# V21-Selector-Keyboard-Relay-K-R-RevD-S.net
KiCad netlist of a schematic drawn in EAGLE
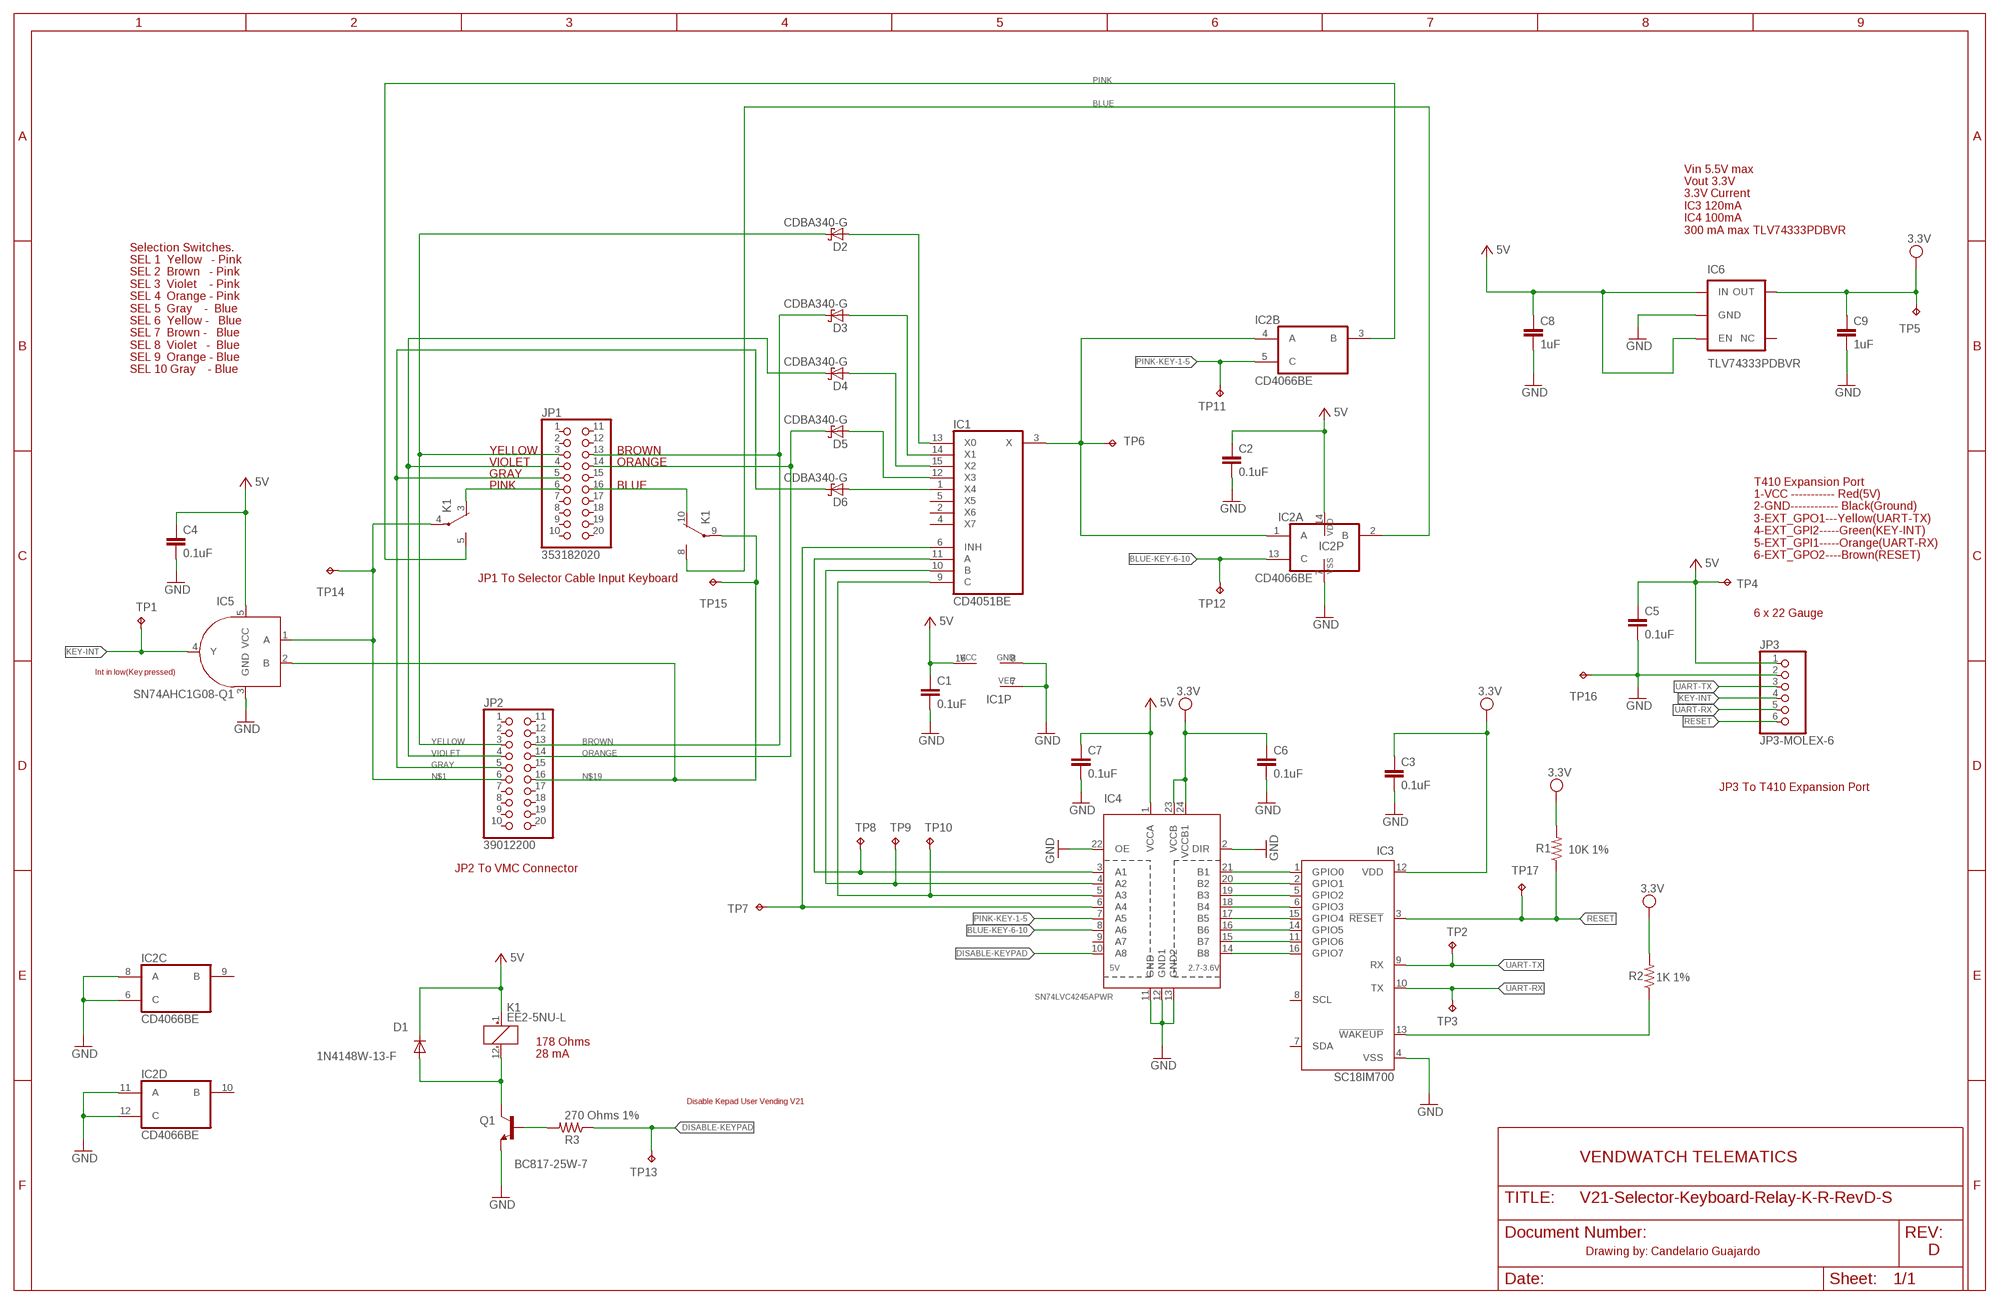
[diagram p0: schematic, sheet 1]

(export (version "E")
  (design (tool "Eeschema 10.0.6"))
  (components
    (comp (ref "C1")
      (value "0.1uF")
      (footprint "eagle-import:0805")
      (libsource (lib "eagle-import") (part "CAP0805"))
    )
    (comp (ref "C2")
      (value "0.1uF")
      (footprint "eagle-import:0805")
      (libsource (lib "eagle-import") (part "CAP0805"))
    )
    (comp (ref "C3")
      (value "0.1uF")
      (footprint "eagle-import:0805")
      (libsource (lib "eagle-import") (part "CAP0805"))
    )
    (comp (ref "C4")
      (value "0.1uF")
      (footprint "eagle-import:0805")
      (libsource (lib "eagle-import") (part "CAP0805"))
    )
    (comp (ref "C5")
      (value "0.1uF")
      (footprint "eagle-import:0805")
      (libsource (lib "eagle-import") (part "CAP0805"))
    )
    (comp (ref "C6")
      (value "0.1uF")
      (footprint "eagle-import:0805")
      (libsource (lib "eagle-import") (part "CAP0805"))
    )
    (comp (ref "C7")
      (value "0.1uF")
      (footprint "eagle-import:0805")
      (libsource (lib "eagle-import") (part "CAP0805"))
    )
    (comp (ref "C8")
      (value "1uF")
      (footprint "eagle-import:0805")
      (libsource (lib "eagle-import") (part "CAP0805"))
    )
    (comp (ref "C9")
      (value "1uF")
      (footprint "eagle-import:0805")
      (libsource (lib "eagle-import") (part "CAP0805"))
    )
    (comp (ref "D1")
      (value "1N4148W-13-F")
      (footprint "eagle-import:SOD-123")
      (libsource (lib "eagle-import") (part "DIODESOD-123"))
    )
    (comp (ref "D2")
      (value "CDBA340-G")
      (footprint "eagle-import:DO-214AC-SMA")
      (libsource (lib "eagle-import") (part "CDBA340-G"))
    )
    (comp (ref "D3")
      (value "CDBA340-G")
      (footprint "eagle-import:DO-214AC-SMA")
      (libsource (lib "eagle-import") (part "CDBA340-G"))
    )
    (comp (ref "D4")
      (value "CDBA340-G")
      (footprint "eagle-import:DO-214AC-SMA")
      (libsource (lib "eagle-import") (part "CDBA340-G"))
    )
    (comp (ref "D5")
      (value "CDBA340-G")
      (footprint "eagle-import:DO-214AC-SMA")
      (libsource (lib "eagle-import") (part "CDBA340-G"))
    )
    (comp (ref "D6")
      (value "CDBA340-G")
      (footprint "eagle-import:DO-214AC-SMA")
      (libsource (lib "eagle-import") (part "CDBA340-G"))
    )
    (comp (ref "IC1")
      (value "CD4051BE")
      (footprint "eagle-import:SO16")
      (libsource (lib "eagle-import") (part "4051D"))
    )
    (comp (ref "IC2")
      (value "CD4066BE")
      (footprint "eagle-import:SO14")
      (libsource (lib "eagle-import") (part "4066D"))
    )
    (comp (ref "IC3")
      (value "SC18IM700")
      (footprint "eagle-import:TSSOP16")
      (fields (field (name "MANUFACTURER") "NXP Semiconductors") (field (name "MPN") "SC18IM700IPW/S8HP"))
      (libsource (lib "eagle-import") (part "SC18IM700"))
    )
    (comp (ref "IC4")
      (value "SN74LVC4245APWR")
      (footprint "eagle-import:SOIC24")
      (libsource (lib "eagle-import") (part "SN74LVC4245"))
    )
    (comp (ref "IC5")
      (value "SN74AHC1G08-Q1")
      (footprint "eagle-import:SOT23-5")
      (libsource (lib "eagle-import") (part "74AHC1G08"))
    )
    (comp (ref "IC6")
      (value "TLV74333PDBVR")
      (footprint "eagle-import:SOT-23-5")
      (libsource (lib "eagle-import") (part "TLV74333PDBVR"))
    )
    (comp (ref "JP1")
      (value "353182020")
      (footprint "eagle-import:2X10-4.2MM-TH-RA")
      (libsource (lib "eagle-import") (part "353182020"))
    )
    (comp (ref "JP2")
      (value "39012200")
      (footprint "eagle-import:2X10-4.2MM-FS-CRIMP")
      (libsource (lib "eagle-import") (part "39012200"))
    )
    (comp (ref "JP3")
      (value "JP3-MOLEX-6")
      (footprint "eagle-import:HEADER-1X6-22-GAUGE-OVAL")
      (libsource (lib "eagle-import") (part "JP3-MOLEX-6"))
    )
    (comp (ref "K1")
      (value "EE2-5NU-L")
      (footprint "eagle-import:DPDT-2-FROM-C-EE2")
      (libsource (lib "eagle-import") (part "EE2-5NU-L"))
    )
    (comp (ref "Q1")
      (value "BC817-25W-7")
      (footprint "eagle-import:SOT323")
      (libsource (lib "eagle-import") (part "TRANSISTOR-NPN"))
    )
    (comp (ref "R1")
      (value "10K 1%")
      (footprint "eagle-import:0805")
      (libsource (lib "eagle-import") (part "RESISTOR0805-RES"))
    )
    (comp (ref "R2")
      (value "1K 1%")
      (footprint "eagle-import:0805")
      (libsource (lib "eagle-import") (part "RESISTOR0805-RES"))
    )
    (comp (ref "R3")
      (value "270 Ohms 1%")
      (footprint "eagle-import:0805")
      (libsource (lib "eagle-import") (part "RESISTOR0805-RES"))
    )
    (comp (ref "TP1")
      (value "TPB1,27")
      (footprint "eagle-import:B1,27")
      (libsource (lib "eagle-import") (part "TPB1,27"))
    )
    (comp (ref "TP2")
      (value "TPB1,27")
      (footprint "eagle-import:B1,27")
      (libsource (lib "eagle-import") (part "TPB1,27"))
    )
    (comp (ref "TP3")
      (value "TPB1,27")
      (footprint "eagle-import:B1,27")
      (libsource (lib "eagle-import") (part "TPB1,27"))
    )
    (comp (ref "TP4")
      (value "TPB1,27")
      (footprint "eagle-import:B1,27")
      (libsource (lib "eagle-import") (part "TPB1,27"))
    )
    (comp (ref "TP5")
      (value "TPB1,27")
      (footprint "eagle-import:B1,27")
      (libsource (lib "eagle-import") (part "TPB1,27"))
    )
    (comp (ref "TP6")
      (value "TPB1,27")
      (footprint "eagle-import:B1,27")
      (libsource (lib "eagle-import") (part "TPB1,27"))
    )
    (comp (ref "TP7")
      (value "TPB1,27")
      (footprint "eagle-import:B1,27")
      (libsource (lib "eagle-import") (part "TPB1,27"))
    )
    (comp (ref "TP8")
      (value "TPB1,27")
      (footprint "eagle-import:B1,27")
      (libsource (lib "eagle-import") (part "TPB1,27"))
    )
    (comp (ref "TP9")
      (value "TPB1,27")
      (footprint "eagle-import:B1,27")
      (libsource (lib "eagle-import") (part "TPB1,27"))
    )
    (comp (ref "TP10")
      (value "TPB1,27")
      (footprint "eagle-import:B1,27")
      (libsource (lib "eagle-import") (part "TPB1,27"))
    )
    (comp (ref "TP11")
      (value "TPB1,27")
      (footprint "eagle-import:B1,27")
      (libsource (lib "eagle-import") (part "TPB1,27"))
    )
    (comp (ref "TP12")
      (value "TPB1,27")
      (footprint "eagle-import:B1,27")
      (libsource (lib "eagle-import") (part "TPB1,27"))
    )
    (comp (ref "TP13")
      (value "TPB1,27")
      (footprint "eagle-import:B1,27")
      (libsource (lib "eagle-import") (part "TPB1,27"))
    )
    (comp (ref "TP14")
      (value "TPB1,27")
      (footprint "eagle-import:B1,27")
      (libsource (lib "eagle-import") (part "TPB1,27"))
    )
    (comp (ref "TP15")
      (value "TPB1,27")
      (footprint "eagle-import:B1,27")
      (libsource (lib "eagle-import") (part "TPB1,27"))
    )
    (comp (ref "TP16")
      (value "TPB1,27")
      (footprint "eagle-import:B1,27")
      (libsource (lib "eagle-import") (part "TPB1,27"))
    )
    (comp (ref "TP17")
      (value "TPB1,27")
      (footprint "eagle-import:B1,27")
      (libsource (lib "eagle-import") (part "TPB1,27"))
    )
  )
  (nets
    (net (code "1") (name "/BLUE") (class "Default")
      (node (ref "IC2") (pin "2") (pinfunction "B_2") (pintype "tri_state"))
      (node (ref "K1") (pin "8") (pinfunction "S_8") (pintype "passive"))
    )
    (net (code "2") (name "/BROWN") (class "Default")
      (node (ref "D3") (pin "K") (pinfunction "C_K") (pintype "passive"))
      (node (ref "JP1") (pin "13") (pinfunction "13_13") (pintype "passive"))
      (node (ref "JP2") (pin "13") (pinfunction "13_13") (pintype "passive"))
    )
    (net (code "3") (name "/GRAY") (class "Default")
      (node (ref "D6") (pin "K") (pinfunction "C_K") (pintype "passive"))
      (node (ref "JP1") (pin "5") (pinfunction "5_5") (pintype "passive"))
      (node (ref "JP2") (pin "5") (pinfunction "5_5") (pintype "passive"))
    )
    (net (code "4") (name "/N$1") (class "Default")
      (node (ref "IC5") (pin "1") (pinfunction "A_1") (pintype "bidirectional"))
      (node (ref "JP2") (pin "6") (pinfunction "6_6") (pintype "passive"))
      (node (ref "K1") (pin "4") (pinfunction "P_4") (pintype "passive"))
      (node (ref "TP14") (pin "TP") (pinfunction "TP_TP") (pintype "input"))
    )
    (net (code "5") (name "/N$19") (class "Default")
      (node (ref "IC5") (pin "2") (pinfunction "B_2") (pintype "bidirectional"))
      (node (ref "JP2") (pin "16") (pinfunction "16_16") (pintype "passive"))
      (node (ref "K1") (pin "9") (pinfunction "P_9") (pintype "passive"))
      (node (ref "TP15") (pin "TP") (pinfunction "TP_TP") (pintype "input"))
    )
    (net (code "6") (name "/ORANGE") (class "Default")
      (node (ref "D5") (pin "K") (pinfunction "C_K") (pintype "passive"))
      (node (ref "JP1") (pin "14") (pinfunction "14_14") (pintype "passive"))
      (node (ref "JP2") (pin "14") (pinfunction "14_14") (pintype "passive"))
    )
    (net (code "7") (name "/PINK") (class "Default")
      (node (ref "IC2") (pin "3") (pinfunction "B_3") (pintype "tri_state"))
      (node (ref "K1") (pin "5") (pinfunction "S_5") (pintype "passive"))
    )
    (net (code "8") (name "/VIOLET") (class "Default")
      (node (ref "D4") (pin "K") (pinfunction "C_K") (pintype "passive"))
      (node (ref "JP1") (pin "4") (pinfunction "4_4") (pintype "passive"))
      (node (ref "JP2") (pin "4") (pinfunction "4_4") (pintype "passive"))
    )
    (net (code "9") (name "/YELLOW") (class "Default")
      (node (ref "D2") (pin "K") (pinfunction "C_K") (pintype "passive"))
      (node (ref "JP1") (pin "3") (pinfunction "3_3") (pintype "passive"))
      (node (ref "JP2") (pin "3") (pinfunction "3_3") (pintype "passive"))
    )
    (net (code "10") (name "3.3V") (class "Default")
      (node (ref "C3") (pin "1") (pinfunction "1_1") (pintype "passive"))
      (node (ref "C6") (pin "1") (pinfunction "1_1") (pintype "passive"))
      (node (ref "C9") (pin "1") (pinfunction "1_1") (pintype "passive"))
      (node (ref "IC3") (pin "12") (pinfunction "VDD_12") (pintype "power_in"))
      (node (ref "IC4") (pin "23") (pinfunction "VCCB_23") (pintype "bidirectional"))
      (node (ref "IC4") (pin "24") (pinfunction "VCCB1_24") (pintype "bidirectional"))
      (node (ref "IC6") (pin "5") (pinfunction "OUT_5") (pintype "output"))
      (node (ref "R1") (pin "2") (pinfunction "2_2") (pintype "passive"))
      (node (ref "R2") (pin "2") (pinfunction "2_2") (pintype "passive"))
      (node (ref "TP5") (pin "TP") (pinfunction "TP_TP") (pintype "input"))
    )
    (net (code "11") (name "5V") (class "Default")
      (node (ref "C1") (pin "1") (pinfunction "1_1") (pintype "passive"))
      (node (ref "C2") (pin "1") (pinfunction "1_1") (pintype "passive"))
      (node (ref "C4") (pin "1") (pinfunction "1_1") (pintype "passive"))
      (node (ref "C5") (pin "1") (pinfunction "1_1") (pintype "passive"))
      (node (ref "C7") (pin "1") (pinfunction "1_1") (pintype "passive"))
      (node (ref "C8") (pin "1") (pinfunction "1_1") (pintype "passive"))
      (node (ref "D1") (pin "C") (pinfunction "C_C") (pintype "passive"))
      (node (ref "IC1") (pin "16") (pinfunction "VCC_16") (pintype "power_in"))
      (node (ref "IC2") (pin "14") (pinfunction "VDD_14") (pintype "power_in"))
      (node (ref "IC4") (pin "1") (pinfunction "VCCA_1") (pintype "bidirectional"))
      (node (ref "IC5") (pin "5") (pinfunction "VCC_5") (pintype "bidirectional"))
      (node (ref "IC6") (pin "1") (pinfunction "IN_1") (pintype "input"))
      (node (ref "IC6") (pin "3") (pinfunction "EN_3") (pintype "input"))
      (node (ref "JP3") (pin "1") (pinfunction "1_1") (pintype "passive"))
      (node (ref "K1") (pin "1") (pinfunction "+_1") (pintype "passive"))
      (node (ref "TP4") (pin "TP") (pinfunction "TP_TP") (pintype "input"))
    )
    (net (code "12") (name "BLUE-KEY-6-10") (class "Default")
      (node (ref "IC2") (pin "13") (pinfunction "C_13") (pintype "input"))
      (node (ref "IC4") (pin "8") (pinfunction "A6_8") (pintype "bidirectional"))
      (node (ref "TP12") (pin "TP") (pinfunction "TP_TP") (pintype "input"))
    )
    (net (code "13") (name "DISABLE-KEYPAD") (class "Default")
      (node (ref "IC4") (pin "10") (pinfunction "A8_10") (pintype "bidirectional"))
      (node (ref "R3") (pin "1") (pinfunction "1_1") (pintype "passive"))
      (node (ref "TP13") (pin "TP") (pinfunction "TP_TP") (pintype "input"))
    )
    (net (code "14") (name "GND") (class "Default")
      (node (ref "C1") (pin "2") (pinfunction "2_2") (pintype "passive"))
      (node (ref "C2") (pin "2") (pinfunction "2_2") (pintype "passive"))
      (node (ref "C3") (pin "2") (pinfunction "2_2") (pintype "passive"))
      (node (ref "C4") (pin "2") (pinfunction "2_2") (pintype "passive"))
      (node (ref "C5") (pin "2") (pinfunction "2_2") (pintype "passive"))
      (node (ref "C6") (pin "2") (pinfunction "2_2") (pintype "passive"))
      (node (ref "C7") (pin "2") (pinfunction "2_2") (pintype "passive"))
      (node (ref "C8") (pin "2") (pinfunction "2_2") (pintype "passive"))
      (node (ref "C9") (pin "2") (pinfunction "2_2") (pintype "passive"))
      (node (ref "IC1") (pin "7") (pinfunction "VEE_7") (pintype "power_in"))
      (node (ref "IC1") (pin "8") (pinfunction "GND_8") (pintype "power_in"))
      (node (ref "IC2") (pin "11") (pinfunction "A_11") (pintype "tri_state"))
      (node (ref "IC2") (pin "12") (pinfunction "C_12") (pintype "input"))
      (node (ref "IC2") (pin "6") (pinfunction "C_6") (pintype "input"))
      (node (ref "IC2") (pin "7") (pinfunction "VSS_7") (pintype "power_in"))
      (node (ref "IC2") (pin "8") (pinfunction "A_8") (pintype "tri_state"))
      (node (ref "IC3") (pin "4") (pinfunction "VSS_4") (pintype "power_in"))
      (node (ref "IC4") (pin "11") (pinfunction "GND_11") (pintype "bidirectional"))
      (node (ref "IC4") (pin "12") (pinfunction "GND1_12") (pintype "bidirectional"))
      (node (ref "IC4") (pin "13") (pinfunction "GND2_13") (pintype "bidirectional"))
      (node (ref "IC4") (pin "2") (pinfunction "DIR_2") (pintype "bidirectional"))
      (node (ref "IC4") (pin "22") (pinfunction "OE_22") (pintype "bidirectional"))
      (node (ref "IC5") (pin "3") (pinfunction "GND_3") (pintype "bidirectional"))
      (node (ref "IC6") (pin "2") (pinfunction "GND_2") (pintype "power_in"))
      (node (ref "JP3") (pin "2") (pinfunction "2_2") (pintype "passive"))
      (node (ref "Q1") (pin "2") (pinfunction "E_2") (pintype "passive"))
      (node (ref "TP16") (pin "TP") (pinfunction "TP_TP") (pintype "input"))
    )
    (net (code "15") (name "KEY-INT") (class "Default")
      (node (ref "IC5") (pin "4") (pinfunction "Y_4") (pintype "bidirectional"))
      (node (ref "JP3") (pin "4") (pinfunction "4_4") (pintype "passive"))
      (node (ref "TP1") (pin "TP") (pinfunction "TP_TP") (pintype "input"))
    )
    (net (code "16") (name "Net-(IC1A-A)") (class "Default")
      (node (ref "IC1") (pin "11") (pinfunction "A_11") (pintype "input"))
      (node (ref "IC4") (pin "3") (pinfunction "A1_3") (pintype "bidirectional"))
      (node (ref "TP8") (pin "TP") (pinfunction "TP_TP") (pintype "input"))
    )
    (net (code "17") (name "Net-(IC1A-B)") (class "Default")
      (node (ref "IC1") (pin "10") (pinfunction "B_10") (pintype "input"))
      (node (ref "IC4") (pin "4") (pinfunction "A2_4") (pintype "bidirectional"))
      (node (ref "TP9") (pin "TP") (pinfunction "TP_TP") (pintype "input"))
    )
    (net (code "18") (name "Net-(IC1A-C)") (class "Default")
      (node (ref "IC1") (pin "9") (pinfunction "C_9") (pintype "input"))
      (node (ref "IC4") (pin "5") (pinfunction "A3_5") (pintype "bidirectional"))
      (node (ref "TP10") (pin "TP") (pinfunction "TP_TP") (pintype "input"))
    )
    (net (code "19") (name "Net-(IC1A-INH)") (class "Default")
      (node (ref "IC1") (pin "6") (pinfunction "INH_6") (pintype "input"))
      (node (ref "IC4") (pin "6") (pinfunction "A4_6") (pintype "bidirectional"))
      (node (ref "TP7") (pin "TP") (pinfunction "TP_TP") (pintype "input"))
    )
    (net (code "20") (name "Net-(IC1A-X)") (class "Default")
      (node (ref "IC1") (pin "3") (pinfunction "X_3") (pintype "bidirectional"))
      (node (ref "IC2") (pin "1") (pinfunction "A_1") (pintype "tri_state"))
      (node (ref "IC2") (pin "4") (pinfunction "A_4") (pintype "tri_state"))
      (node (ref "TP6") (pin "TP") (pinfunction "TP_TP") (pintype "input"))
    )
    (net (code "21") (name "Net-(IC1A-X0)") (class "Default")
      (node (ref "D2") (pin "A") (pinfunction "A_A") (pintype "passive"))
      (node (ref "IC1") (pin "13") (pinfunction "X0_13") (pintype "bidirectional"))
    )
    (net (code "22") (name "Net-(IC1A-X1)") (class "Default")
      (node (ref "D3") (pin "A") (pinfunction "A_A") (pintype "passive"))
      (node (ref "IC1") (pin "14") (pinfunction "X1_14") (pintype "bidirectional"))
    )
    (net (code "23") (name "Net-(IC1A-X2)") (class "Default")
      (node (ref "D4") (pin "A") (pinfunction "A_A") (pintype "passive"))
      (node (ref "IC1") (pin "15") (pinfunction "X2_15") (pintype "bidirectional"))
    )
    (net (code "24") (name "Net-(IC1A-X3)") (class "Default")
      (node (ref "D5") (pin "A") (pinfunction "A_A") (pintype "passive"))
      (node (ref "IC1") (pin "12") (pinfunction "X3_12") (pintype "bidirectional"))
    )
    (net (code "25") (name "Net-(IC1A-X4)") (class "Default")
      (node (ref "D6") (pin "A") (pinfunction "A_A") (pintype "passive"))
      (node (ref "IC1") (pin "1") (pinfunction "X4_1") (pintype "bidirectional"))
    )
    (net (code "26") (name "Net-(IC3-GPIO0)") (class "Default")
      (node (ref "IC3") (pin "1") (pinfunction "GPIO0_1") (pintype "bidirectional"))
      (node (ref "IC4") (pin "21") (pinfunction "B1_21") (pintype "bidirectional"))
    )
    (net (code "27") (name "Net-(IC3-GPIO1)") (class "Default")
      (node (ref "IC3") (pin "2") (pinfunction "GPIO1_2") (pintype "bidirectional"))
      (node (ref "IC4") (pin "20") (pinfunction "B2_20") (pintype "bidirectional"))
    )
    (net (code "28") (name "Net-(IC3-GPIO2)") (class "Default")
      (node (ref "IC3") (pin "5") (pinfunction "GPIO2_5") (pintype "bidirectional"))
      (node (ref "IC4") (pin "19") (pinfunction "B3_19") (pintype "bidirectional"))
    )
    (net (code "29") (name "Net-(IC3-GPIO3)") (class "Default")
      (node (ref "IC3") (pin "6") (pinfunction "GPIO3_6") (pintype "bidirectional"))
      (node (ref "IC4") (pin "18") (pinfunction "B4_18") (pintype "bidirectional"))
    )
    (net (code "30") (name "Net-(IC3-GPIO4)") (class "Default")
      (node (ref "IC3") (pin "15") (pinfunction "GPIO4_15") (pintype "bidirectional"))
      (node (ref "IC4") (pin "17") (pinfunction "B5_17") (pintype "bidirectional"))
    )
    (net (code "31") (name "Net-(IC3-GPIO5)") (class "Default")
      (node (ref "IC3") (pin "14") (pinfunction "GPIO5_14") (pintype "bidirectional"))
      (node (ref "IC4") (pin "16") (pinfunction "B6_16") (pintype "bidirectional"))
    )
    (net (code "32") (name "Net-(IC3-GPIO6)") (class "Default")
      (node (ref "IC3") (pin "11") (pinfunction "GPIO6_11") (pintype "bidirectional"))
      (node (ref "IC4") (pin "15") (pinfunction "B7_15") (pintype "bidirectional"))
    )
    (net (code "33") (name "Net-(IC3-GPIO7)") (class "Default")
      (node (ref "IC3") (pin "16") (pinfunction "GPIO7_16") (pintype "bidirectional"))
      (node (ref "IC4") (pin "14") (pinfunction "B8_14") (pintype "bidirectional"))
    )
    (net (code "34") (name "Net-(IC3-~{WAKEUP})") (class "Default")
      (node (ref "IC3") (pin "13") (pinfunction "~{WAKEUP}_13") (pintype "output"))
      (node (ref "R2") (pin "1") (pinfunction "1_1") (pintype "passive"))
    )
    (net (code "35") (name "Net-(K1A-O)") (class "Default")
      (node (ref "JP1") (pin "6") (pinfunction "6_6") (pintype "passive"))
      (node (ref "K1") (pin "3") (pinfunction "O_3") (pintype "passive"))
    )
    (net (code "36") (name "Net-(K1B-O)") (class "Default")
      (node (ref "JP1") (pin "16") (pinfunction "16_16") (pintype "passive"))
      (node (ref "K1") (pin "10") (pinfunction "O_10") (pintype "passive"))
    )
    (net (code "37") (name "Net-(K1C--)") (class "Default")
      (node (ref "D1") (pin "A") (pinfunction "A_A") (pintype "passive"))
      (node (ref "K1") (pin "12") (pinfunction "-_12") (pintype "passive"))
      (node (ref "Q1") (pin "3") (pinfunction "C_3") (pintype "passive"))
    )
    (net (code "38") (name "Net-(Q1-B)") (class "Default")
      (node (ref "Q1") (pin "1") (pinfunction "B_1") (pintype "passive"))
      (node (ref "R3") (pin "2") (pinfunction "2_2") (pintype "passive"))
    )
    (net (code "39") (name "PINK-KEY-1-5") (class "Default")
      (node (ref "IC2") (pin "5") (pinfunction "C_5") (pintype "input"))
      (node (ref "IC4") (pin "7") (pinfunction "A5_7") (pintype "bidirectional"))
      (node (ref "TP11") (pin "TP") (pinfunction "TP_TP") (pintype "input"))
    )
    (net (code "40") (name "RESET") (class "Default")
      (node (ref "IC3") (pin "3") (pinfunction "~{RESET}_3") (pintype "input"))
      (node (ref "JP3") (pin "6") (pinfunction "6_6") (pintype "passive"))
      (node (ref "R1") (pin "1") (pinfunction "1_1") (pintype "passive"))
      (node (ref "TP17") (pin "TP") (pinfunction "TP_TP") (pintype "input"))
    )
    (net (code "41") (name "UART-RX") (class "Default")
      (node (ref "IC3") (pin "10") (pinfunction "TX_10") (pintype "output"))
      (node (ref "JP3") (pin "5") (pinfunction "5_5") (pintype "passive"))
      (node (ref "TP3") (pin "TP") (pinfunction "TP_TP") (pintype "input"))
    )
    (net (code "42") (name "UART-TX") (class "Default")
      (node (ref "IC3") (pin "9") (pinfunction "RX_9") (pintype "input"))
      (node (ref "JP3") (pin "3") (pinfunction "3_3") (pintype "passive"))
      (node (ref "TP2") (pin "TP") (pinfunction "TP_TP") (pintype "input"))
    )
    (net (code "43") (name "unconnected-(IC1A-X5-Pad5)") (class "Default")
      (node (ref "IC1") (pin "5") (pinfunction "X5_5") (pintype "bidirectional"))
    )
    (net (code "44") (name "unconnected-(IC1A-X6-Pad2)") (class "Default")
      (node (ref "IC1") (pin "2") (pinfunction "X6_2") (pintype "bidirectional"))
    )
    (net (code "45") (name "unconnected-(IC1A-X7-Pad4)") (class "Default")
      (node (ref "IC1") (pin "4") (pinfunction "X7_4") (pintype "bidirectional"))
    )
    (net (code "46") (name "unconnected-(IC2C-B-Pad9)") (class "Default")
      (node (ref "IC2") (pin "9") (pinfunction "B_9") (pintype "tri_state"))
    )
    (net (code "47") (name "unconnected-(IC2D-B-Pad10)") (class "Default")
      (node (ref "IC2") (pin "10") (pinfunction "B_10") (pintype "tri_state"))
    )
    (net (code "48") (name "unconnected-(IC3-SCL-Pad8)") (class "Default")
      (node (ref "IC3") (pin "8") (pinfunction "SCL_8") (pintype "output"))
    )
    (net (code "49") (name "unconnected-(IC3-SDA-Pad7)") (class "Default")
      (node (ref "IC3") (pin "7") (pinfunction "SDA_7") (pintype "bidirectional"))
    )
    (net (code "50") (name "unconnected-(IC4-A7-Pad9)") (class "Default")
      (node (ref "IC4") (pin "9") (pinfunction "A7_9") (pintype "bidirectional"))
    )
    (net (code "51") (name "unconnected-(IC6-NC-Pad4)") (class "Default")
      (node (ref "IC6") (pin "4") (pinfunction "NC_4") (pintype "no_connect"))
    )
    (net (code "52") (name "unconnected-(JP1-Pad1)") (class "Default")
      (node (ref "JP1") (pin "1") (pinfunction "1_1") (pintype "passive"))
    )
    (net (code "53") (name "unconnected-(JP1-Pad2)") (class "Default")
      (node (ref "JP1") (pin "2") (pinfunction "2_2") (pintype "passive"))
    )
    (net (code "54") (name "unconnected-(JP1-Pad7)") (class "Default")
      (node (ref "JP1") (pin "7") (pinfunction "7_7") (pintype "passive"))
    )
    (net (code "55") (name "unconnected-(JP1-Pad8)") (class "Default")
      (node (ref "JP1") (pin "8") (pinfunction "8_8") (pintype "passive"))
    )
    (net (code "56") (name "unconnected-(JP1-Pad9)") (class "Default")
      (node (ref "JP1") (pin "9") (pinfunction "9_9") (pintype "passive"))
    )
    (net (code "57") (name "unconnected-(JP1-Pad10)") (class "Default")
      (node (ref "JP1") (pin "10") (pinfunction "10_10") (pintype "passive"))
    )
    (net (code "58") (name "unconnected-(JP1-Pad11)") (class "Default")
      (node (ref "JP1") (pin "11") (pinfunction "11_11") (pintype "passive"))
    )
    (net (code "59") (name "unconnected-(JP1-Pad12)") (class "Default")
      (node (ref "JP1") (pin "12") (pinfunction "12_12") (pintype "passive"))
    )
    (net (code "60") (name "unconnected-(JP1-Pad15)") (class "Default")
      (node (ref "JP1") (pin "15") (pinfunction "15_15") (pintype "passive"))
    )
    (net (code "61") (name "unconnected-(JP1-Pad17)") (class "Default")
      (node (ref "JP1") (pin "17") (pinfunction "17_17") (pintype "passive"))
    )
    (net (code "62") (name "unconnected-(JP1-Pad18)") (class "Default")
      (node (ref "JP1") (pin "18") (pinfunction "18_18") (pintype "passive"))
    )
    (net (code "63") (name "unconnected-(JP1-Pad19)") (class "Default")
      (node (ref "JP1") (pin "19") (pinfunction "19_19") (pintype "passive"))
    )
    (net (code "64") (name "unconnected-(JP1-Pad20)") (class "Default")
      (node (ref "JP1") (pin "20") (pinfunction "20_20") (pintype "passive"))
    )
    (net (code "65") (name "unconnected-(JP2-Pad1)") (class "Default")
      (node (ref "JP2") (pin "1") (pinfunction "1_1") (pintype "passive"))
    )
    (net (code "66") (name "unconnected-(JP2-Pad2)") (class "Default")
      (node (ref "JP2") (pin "2") (pinfunction "2_2") (pintype "passive"))
    )
    (net (code "67") (name "unconnected-(JP2-Pad7)") (class "Default")
      (node (ref "JP2") (pin "7") (pinfunction "7_7") (pintype "passive"))
    )
    (net (code "68") (name "unconnected-(JP2-Pad8)") (class "Default")
      (node (ref "JP2") (pin "8") (pinfunction "8_8") (pintype "passive"))
    )
    (net (code "69") (name "unconnected-(JP2-Pad9)") (class "Default")
      (node (ref "JP2") (pin "9") (pinfunction "9_9") (pintype "passive"))
    )
    (net (code "70") (name "unconnected-(JP2-Pad10)") (class "Default")
      (node (ref "JP2") (pin "10") (pinfunction "10_10") (pintype "passive"))
    )
    (net (code "71") (name "unconnected-(JP2-Pad11)") (class "Default")
      (node (ref "JP2") (pin "11") (pinfunction "11_11") (pintype "passive"))
    )
    (net (code "72") (name "unconnected-(JP2-Pad12)") (class "Default")
      (node (ref "JP2") (pin "12") (pinfunction "12_12") (pintype "passive"))
    )
    (net (code "73") (name "unconnected-(JP2-Pad15)") (class "Default")
      (node (ref "JP2") (pin "15") (pinfunction "15_15") (pintype "passive"))
    )
    (net (code "74") (name "unconnected-(JP2-Pad17)") (class "Default")
      (node (ref "JP2") (pin "17") (pinfunction "17_17") (pintype "passive"))
    )
    (net (code "75") (name "unconnected-(JP2-Pad18)") (class "Default")
      (node (ref "JP2") (pin "18") (pinfunction "18_18") (pintype "passive"))
    )
    (net (code "76") (name "unconnected-(JP2-Pad19)") (class "Default")
      (node (ref "JP2") (pin "19") (pinfunction "19_19") (pintype "passive"))
    )
    (net (code "77") (name "unconnected-(JP2-Pad20)") (class "Default")
      (node (ref "JP2") (pin "20") (pinfunction "20_20") (pintype "passive"))
    )
  )
)
